# RXMIX-SE.net
KiCad netlist of a schematic drawn in Altium Designer
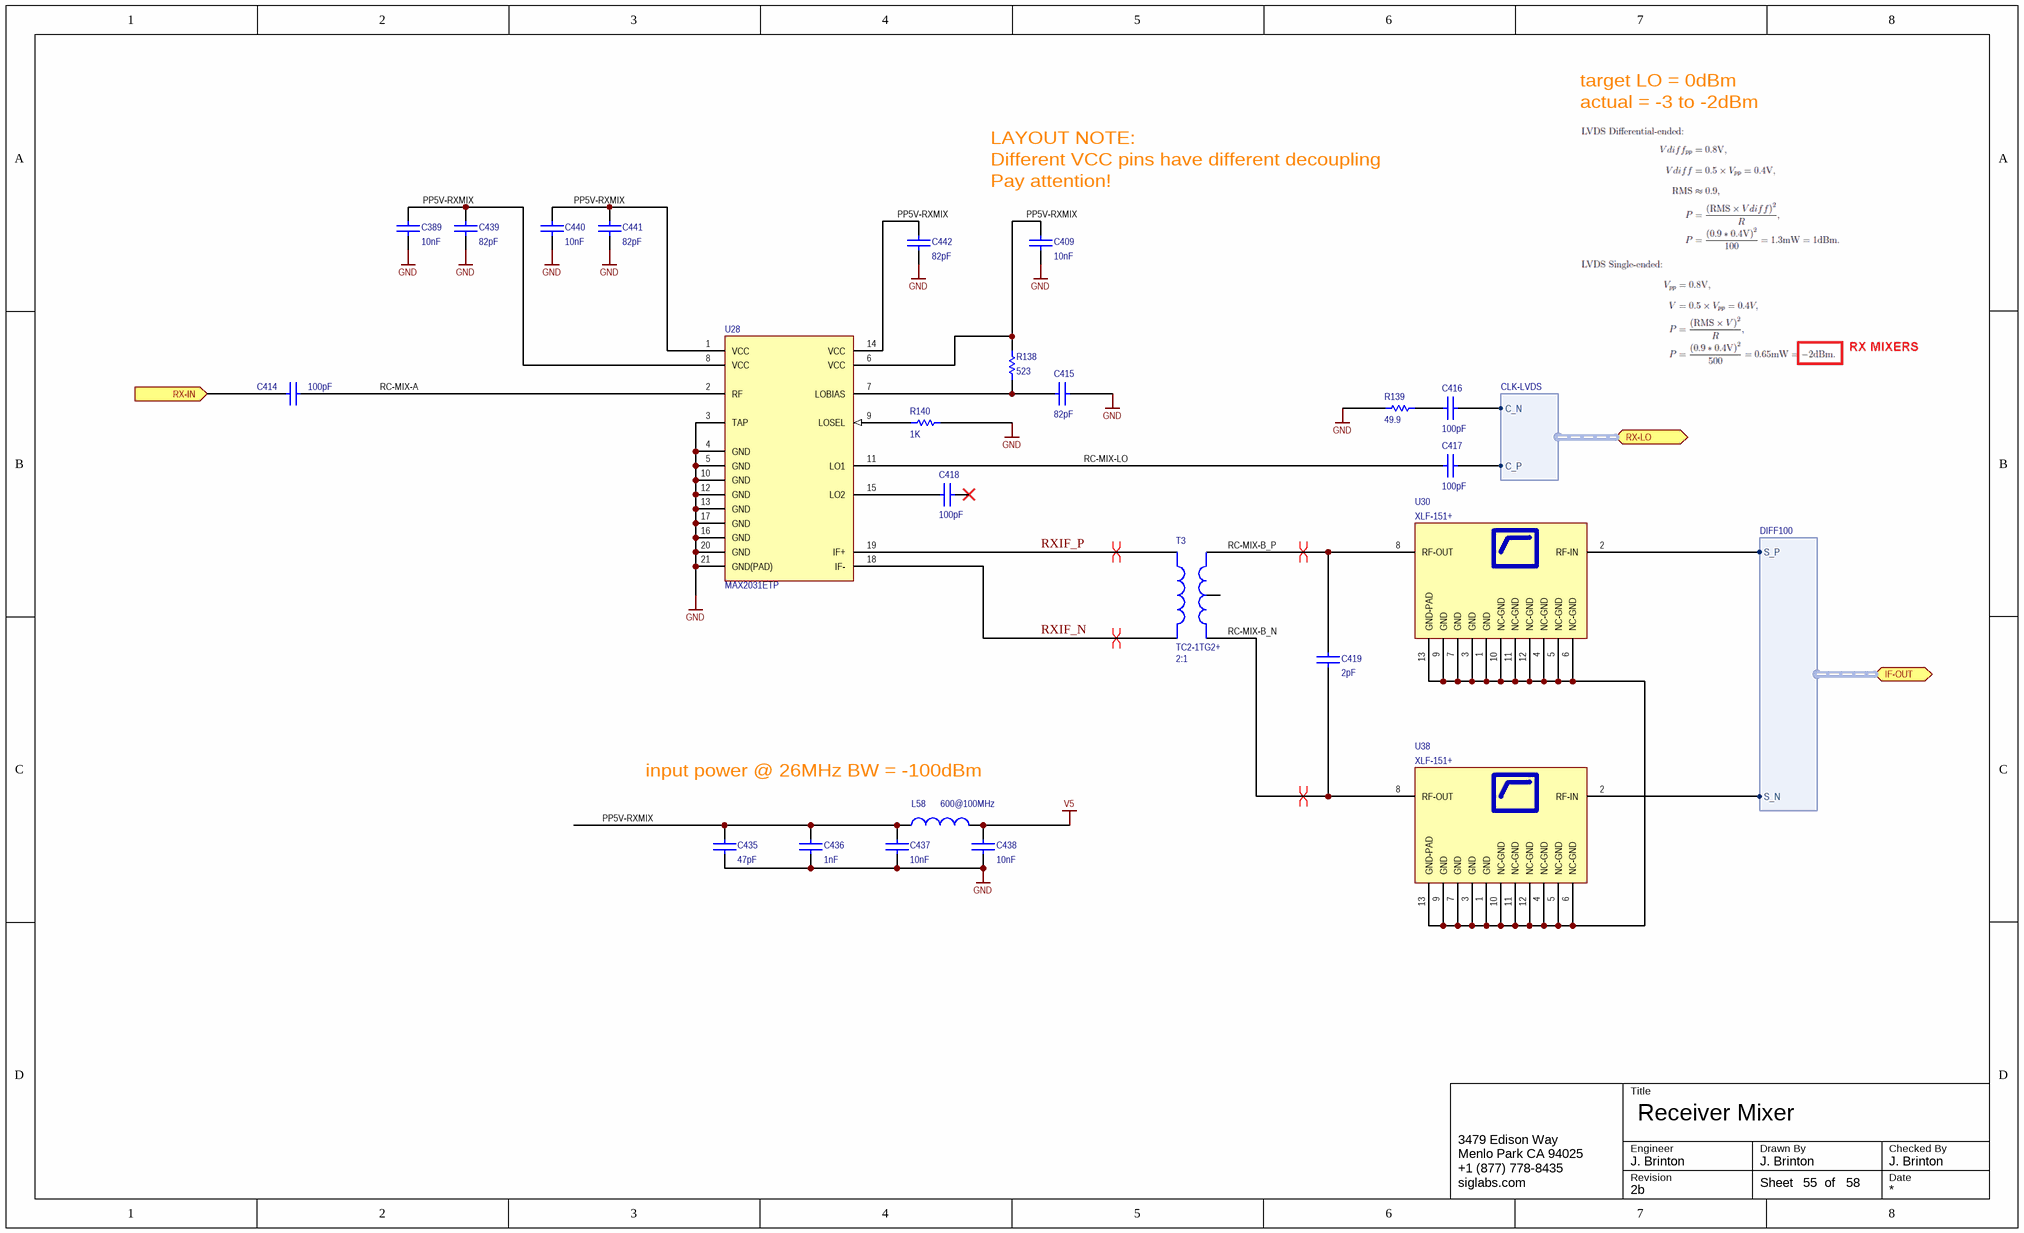
[diagram p0: RXMIX-SE.SchDoc]

(export (version "E")
  (design (tool "Eeschema 10.0.6"))
  (components
    (comp (ref "C389")
      (value "10nF")
      (footprint "generic:0402")
      (description "Ceramic Capacitor 10nF ±10% 25V X7R 0402")
      (fields (field (name "VOLTAGE") "25V") (field (name "MANUFACTURER") "Murata"))
      (libsource (lib "Graviton") (part "CAP 0402"))
    )
    (comp (ref "C409")
      (value "10nF")
      (footprint "generic:0402")
      (description "Ceramic Capacitor 10nF ±10% 25V X7R 0402")
      (fields (field (name "VOLTAGE") "25V") (field (name "MANUFACTURER") "Murata"))
      (libsource (lib "Graviton") (part "CAP 0402"))
    )
    (comp (ref "C414")
      (value "100pF")
      (footprint "0402")
      (description "Ceramic Capacitor 100pF ±1% 25V NP0 0402")
      (fields (field (name "VOLTAGE") "25V") (field (name "MANUFACTURER") "Kemet"))
      (libsource (lib "generic") (part "CAP 0603"))
    )
    (comp (ref "C415")
      (value "82pF")
      (footprint "0402")
      (description "Ceramic Capacitor 82pF ±5% 25V NP0 0402")
      (fields (field (name "VOLTAGE") "25V") (field (name "MANUFACTURER") "Vishay Vitramon"))
      (libsource (lib "generic") (part "CAP"))
    )
    (comp (ref "C416")
      (value "100pF")
      (footprint "0402")
      (description "Ceramic Capacitor 100pF ±1% 25V NP0 0402")
      (fields (field (name "MANUFACTURER") "Kemet") (field (name "VOLTAGE") "25V"))
      (libsource (lib "generic") (part "CAP 0603"))
    )
    (comp (ref "C417")
      (value "100pF")
      (footprint "0402")
      (description "Ceramic Capacitor 100pF ±1% 25V NP0 0402")
      (fields (field (name "VOLTAGE") "25V") (field (name "MANUFACTURER") "Kemet"))
      (libsource (lib "generic") (part "CAP 0603"))
    )
    (comp (ref "C418")
      (value "100pF")
      (footprint "0402")
      (description "Ceramic Capacitor 100pF ±1% 25V NP0 0402")
      (fields (field (name "MANUFACTURER") "Kemet") (field (name "VOLTAGE") "25V"))
      (libsource (lib "generic") (part "CAP 0603"))
    )
    (comp (ref "C419")
      (value "2pF")
      (footprint "generic:0402")
      (description "Ceramic Capacitor 2pF ±0.25pF 50V NP0 0402")
      (fields (field (name "VOLTAGE") "50V") (field (name "MANUFACTURER") "Murata"))
      (libsource (lib "generic") (part "CAP 0402"))
    )
    (comp (ref "C435")
      (value "47pF")
      (footprint "generic:0402")
      (description "Ceramic Capacitor 47pF ±1% 25V NP0 0402")
      (fields (field (name "VOLTAGE") "25V") (field (name "MANUFACTURER") "Kemet"))
      (libsource (lib "Graviton") (part "CAP 0402"))
    )
    (comp (ref "C436")
      (value "1nF")
      (footprint "generic:0402")
      (description "Ceramic Capacitor 1nF ±5% 50V NP0 0402")
      (fields (field (name "VOLTAGE") "50V") (field (name "MANUFACTURER") "Murata"))
      (libsource (lib "Graviton") (part "CAP 0402"))
    )
    (comp (ref "C437")
      (value "10nF")
      (footprint "generic:0402")
      (description "Ceramic Capacitor 10nF ±10% 25V X7R 0402")
      (fields (field (name "VOLTAGE") "25V") (field (name "MANUFACTURER") "Murata"))
      (libsource (lib "Graviton") (part "CAP 0402"))
    )
    (comp (ref "C438")
      (value "10nF")
      (footprint "generic:0402")
      (description "Ceramic Capacitor 10nF ±10% 25V X7R 0402")
      (fields (field (name "VOLTAGE") "25V") (field (name "MANUFACTURER") "Murata"))
      (libsource (lib "Graviton") (part "CAP 0402"))
    )
    (comp (ref "C439")
      (value "82pF")
      (footprint "0402")
      (description "Ceramic Capacitor 82pF ±5% 25V NP0 0402")
      (fields (field (name "MANUFACTURER") "Vishay Vitramon") (field (name "VOLTAGE") "25V"))
      (libsource (lib "generic") (part "CAP"))
    )
    (comp (ref "C440")
      (value "10nF")
      (footprint "generic:0402")
      (description "Ceramic Capacitor 10nF ±10% 25V X7R 0402")
      (fields (field (name "VOLTAGE") "25V") (field (name "MANUFACTURER") "Murata"))
      (libsource (lib "Graviton") (part "CAP 0402"))
    )
    (comp (ref "C441")
      (value "82pF")
      (footprint "0402")
      (description "Ceramic Capacitor 82pF ±5% 25V NP0 0402")
      (fields (field (name "VOLTAGE") "25V") (field (name "MANUFACTURER") "Vishay Vitramon"))
      (libsource (lib "generic") (part "CAP"))
    )
    (comp (ref "C442")
      (value "82pF")
      (footprint "0402")
      (description "Ceramic Capacitor 82pF ±5% 25V NP0 0402")
      (fields (field (name "MANUFACTURER") "Vishay Vitramon") (field (name "VOLTAGE") "25V"))
      (libsource (lib "generic") (part "CAP"))
    )
    (comp (ref "L58")
      (value "600@100MHz")
      (footprint "0402")
      (description "Ferrite Bead 600-Ohm @ 100MHz 900mA 0402")
      (fields (field (name "MANUFACTURER") "Murata") (field (name "TOLERANCE") "±25%"))
      (libsource (lib "Graviton") (part "IND 0402"))
    )
    (comp (ref "R138")
      (value "523")
      (footprint "generic:0603")
      (description "Thick Film Resistor 523 ±1% 0603")
      (fields (field (name "MANUFACTURER") "Yageo") (field (name "TOLERANCE") "±1%"))
      (libsource (lib "generic") (part "RES 0603"))
    )
    (comp (ref "R139")
      (value "49.9")
      (footprint "generic:0603")
      (description "Thick Film Resistor 49.9 ±1% 0603")
      (fields (field (name "MANUFACTURER") "Panasonic") (field (name "TOLERANCE") "±1%"))
      (libsource (lib "generic") (part "RES 0603"))
    )
    (comp (ref "R140")
      (value "1K")
      (footprint "generic:0402")
      (description "Thick Film Resistor 1k ±1% 0402")
      (fields (field (name "MANUFACTURER") "Yageo") (field (name "TOLERANCE") "±1%"))
      (libsource (lib "Graviton") (part "RES 0402"))
    )
    (comp (ref "T3")
      (value "2:1")
      (footprint "AT224-1A")
      (description "RF Transformer 0.4 to 500MHz SMD")
      (fields
        (field (name "MANUFACTURER P/N") "TC2-1TG2+")
        (field (name "MANUFACTURER") "Mini-Circuits")
        (field (name "Comment") "TC2-1TG2+")
      )
      (libsource (lib "phase4") (part "TC1-1TG2+"))
    )
    (comp (ref "U28")
      (value "MAX2031ETP")
      (footprint "QFN21P65_500X500X80L55X30T320N")
      (description "Upconversion/Downconversion Mixer")
      (fields (field (name "MANUFACTURER") "Maxim"))
      (libsource (lib "maxim") (part "MAX2031ETP"))
    )
    (comp (ref "U30")
      (value "XLF-151+")
      (footprint "QFN-XLF-12")
      (description "Reflectionless Low-Pass Filter, DC-150Mhz")
      (fields (field (name "MANUFACTURER") "Mini-Circuits"))
      (libsource (lib "Mini-Circuits") (part "XLF-151+"))
    )
    (comp (ref "U38")
      (value "XLF-151+")
      (footprint "QFN-XLF-12")
      (description "Reflectionless Low-Pass Filter, DC-150Mhz")
      (fields (field (name "MANUFACTURER") "Mini-Circuits"))
      (libsource (lib "Mini-Circuits") (part "XLF-151+"))
    )
  )
  (nets
    (net (code "3") (name "/C_N") (class "Default")
      (node (ref "C416") (pin "2") (pinfunction "2_2") (pintype "passive"))
    )
    (net (code "4") (name "/C_P") (class "Default")
      (node (ref "C417") (pin "2") (pinfunction "2_2") (pintype "passive"))
    )
    (net (code "5") (name "/PP5V-RXMIX") (class "Default")
      (node (ref "C389") (pin "2") (pinfunction "2_2") (pintype "passive"))
      (node (ref "C409") (pin "2") (pinfunction "2_2") (pintype "passive"))
      (node (ref "C435") (pin "2") (pinfunction "2_2") (pintype "passive"))
      (node (ref "C436") (pin "2") (pinfunction "2_2") (pintype "passive"))
      (node (ref "C437") (pin "2") (pinfunction "2_2") (pintype "passive"))
      (node (ref "C439") (pin "2") (pinfunction "2_2") (pintype "passive"))
      (node (ref "C440") (pin "2") (pinfunction "2_2") (pintype "passive"))
      (node (ref "C441") (pin "2") (pinfunction "2_2") (pintype "passive"))
      (node (ref "C442") (pin "2") (pinfunction "2_2") (pintype "passive"))
      (node (ref "L58") (pin "2") (pinfunction "2_2") (pintype "passive"))
      (node (ref "R138") (pin "1") (pinfunction "1_1") (pintype "passive"))
      (node (ref "U28") (pin "1") (pinfunction "VCC_1") (pintype "power_in"))
      (node (ref "U28") (pin "14") (pinfunction "VCC_14") (pintype "power_in"))
      (node (ref "U28") (pin "6") (pinfunction "VCC_6") (pintype "power_in"))
      (node (ref "U28") (pin "8") (pinfunction "VCC_8") (pintype "power_in"))
    )
    (net (code "6") (name "/RC-MIX-A") (class "Default")
      (node (ref "C414") (pin "2") (pinfunction "2_2") (pintype "passive"))
      (node (ref "U28") (pin "2") (pinfunction "RF_2") (pintype "passive"))
    )
    (net (code "7") (name "/RC-MIX-B_N") (class "Default")
      (node (ref "C419") (pin "1") (pinfunction "1_1") (pintype "passive"))
      (node (ref "T3") (pin "1") (pinfunction "Sec+_1") (pintype "passive"))
      (node (ref "U38") (pin "8") (pinfunction "RF-OUT_8") (pintype "passive"))
    )
    (net (code "8") (name "/RC-MIX-B_P") (class "Default")
      (node (ref "C419") (pin "2") (pinfunction "2_2") (pintype "passive"))
      (node (ref "T3") (pin "3") (pinfunction "Sec-_3") (pintype "passive"))
      (node (ref "U30") (pin "8") (pinfunction "RF-OUT_8") (pintype "passive"))
    )
    (net (code "9") (name "/RC-MIX-LO") (class "Default")
      (node (ref "C417") (pin "1") (pinfunction "1_1") (pintype "passive"))
      (node (ref "U28") (pin "11") (pinfunction "LO1_11") (pintype "passive"))
    )
    (net (code "10") (name "/RX-IN") (class "Default")
      (node (ref "C414") (pin "1") (pinfunction "1_1") (pintype "passive"))
    )
    (net (code "11") (name "/RXIF_N") (class "Default")
      (node (ref "T3") (pin "6") (pinfunction "Pri+_6") (pintype "passive"))
      (node (ref "U28") (pin "18") (pinfunction "IF-_18") (pintype "passive"))
    )
    (net (code "12") (name "/RXIF_P") (class "Default")
      (node (ref "T3") (pin "4") (pinfunction "Pri-_4") (pintype "passive"))
      (node (ref "U28") (pin "19") (pinfunction "IF+_19") (pintype "passive"))
    )
    (net (code "13") (name "/S_N") (class "Default")
      (node (ref "U38") (pin "2") (pinfunction "RF-IN_2") (pintype "passive"))
    )
    (net (code "14") (name "/S_P") (class "Default")
      (node (ref "U30") (pin "2") (pinfunction "RF-IN_2") (pintype "passive"))
    )
    (net (code "17") (name "GND") (class "Default")
      (node (ref "C389") (pin "1") (pinfunction "1_1") (pintype "passive"))
      (node (ref "C409") (pin "1") (pinfunction "1_1") (pintype "passive"))
      (node (ref "C415") (pin "2") (pinfunction "2_2") (pintype "passive"))
      (node (ref "C435") (pin "1") (pinfunction "1_1") (pintype "passive"))
      (node (ref "C436") (pin "1") (pinfunction "1_1") (pintype "passive"))
      (node (ref "C437") (pin "1") (pinfunction "1_1") (pintype "passive"))
      (node (ref "C438") (pin "1") (pinfunction "1_1") (pintype "passive"))
      (node (ref "C439") (pin "1") (pinfunction "1_1") (pintype "passive"))
      (node (ref "C440") (pin "1") (pinfunction "1_1") (pintype "passive"))
      (node (ref "C441") (pin "1") (pinfunction "1_1") (pintype "passive"))
      (node (ref "C442") (pin "1") (pinfunction "1_1") (pintype "passive"))
      (node (ref "R139") (pin "1") (pinfunction "1_1") (pintype "passive"))
      (node (ref "R140") (pin "2") (pinfunction "2_2") (pintype "passive"))
      (node (ref "U28") (pin "10") (pinfunction "GND_10") (pintype "power_in"))
      (node (ref "U28") (pin "12") (pinfunction "GND_12") (pintype "power_in"))
      (node (ref "U28") (pin "13") (pinfunction "GND_13") (pintype "power_in"))
      (node (ref "U28") (pin "16") (pinfunction "GND_16") (pintype "power_in"))
      (node (ref "U28") (pin "17") (pinfunction "GND_17") (pintype "power_in"))
      (node (ref "U28") (pin "20") (pinfunction "GND_20") (pintype "power_in"))
      (node (ref "U28") (pin "21") (pinfunction "GND(PAD)_21") (pintype "power_in"))
      (node (ref "U28") (pin "3") (pinfunction "TAP_3") (pintype "passive"))
      (node (ref "U28") (pin "4") (pinfunction "GND_4") (pintype "power_in"))
      (node (ref "U28") (pin "5") (pinfunction "GND_5") (pintype "power_in"))
    )
    (net (code "18") (name "Net-(C416-Pad1)") (class "Default")
      (node (ref "C416") (pin "1") (pinfunction "1_1") (pintype "passive"))
      (node (ref "R139") (pin "2") (pinfunction "2_2") (pintype "passive"))
    )
    (net (code "19") (name "Net-(U28-LO2)") (class "Default")
      (node (ref "C418") (pin "1") (pinfunction "1_1") (pintype "passive"))
      (node (ref "U28") (pin "15") (pinfunction "LO2_15") (pintype "passive"))
    )
    (net (code "20") (name "Net-(U28-LOBIAS)") (class "Default")
      (node (ref "C415") (pin "1") (pinfunction "1_1") (pintype "passive"))
      (node (ref "R138") (pin "2") (pinfunction "2_2") (pintype "passive"))
      (node (ref "U28") (pin "7") (pinfunction "LOBIAS_7") (pintype "passive"))
    )
    (net (code "21") (name "Net-(U28-LOSEL)") (class "Default")
      (node (ref "R140") (pin "1") (pinfunction "1_1") (pintype "passive"))
      (node (ref "U28") (pin "9") (pinfunction "LOSEL_9") (pintype "input"))
    )
    (net (code "22") (name "Net-(U30-GND-PAD)") (class "Default")
      (node (ref "U30") (pin "1") (pinfunction "GND_1") (pintype "passive"))
      (node (ref "U30") (pin "10") (pinfunction "NC-GND_10") (pintype "passive"))
      (node (ref "U30") (pin "11") (pinfunction "NC-GND_11") (pintype "passive"))
      (node (ref "U30") (pin "12") (pinfunction "NC-GND_12") (pintype "passive"))
      (node (ref "U30") (pin "13") (pinfunction "GND-PAD_13") (pintype "passive"))
      (node (ref "U30") (pin "3") (pinfunction "GND_3") (pintype "passive"))
      (node (ref "U30") (pin "4") (pinfunction "NC-GND_4") (pintype "passive"))
      (node (ref "U30") (pin "5") (pinfunction "NC-GND_5") (pintype "passive"))
      (node (ref "U30") (pin "6") (pinfunction "NC-GND_6") (pintype "passive"))
      (node (ref "U30") (pin "7") (pinfunction "GND_7") (pintype "passive"))
      (node (ref "U30") (pin "9") (pinfunction "GND_9") (pintype "passive"))
      (node (ref "U38") (pin "1") (pinfunction "GND_1") (pintype "passive"))
      (node (ref "U38") (pin "10") (pinfunction "NC-GND_10") (pintype "passive"))
      (node (ref "U38") (pin "11") (pinfunction "NC-GND_11") (pintype "passive"))
      (node (ref "U38") (pin "12") (pinfunction "NC-GND_12") (pintype "passive"))
      (node (ref "U38") (pin "13") (pinfunction "GND-PAD_13") (pintype "passive"))
      (node (ref "U38") (pin "3") (pinfunction "GND_3") (pintype "passive"))
      (node (ref "U38") (pin "4") (pinfunction "NC-GND_4") (pintype "passive"))
      (node (ref "U38") (pin "5") (pinfunction "NC-GND_5") (pintype "passive"))
      (node (ref "U38") (pin "6") (pinfunction "NC-GND_6") (pintype "passive"))
      (node (ref "U38") (pin "7") (pinfunction "GND_7") (pintype "passive"))
      (node (ref "U38") (pin "9") (pinfunction "GND_9") (pintype "passive"))
    )
    (net (code "23") (name "V5") (class "Default")
      (node (ref "C438") (pin "2") (pinfunction "2_2") (pintype "passive"))
      (node (ref "L58") (pin "1") (pinfunction "1_1") (pintype "passive"))
    )
    (net (code "24") (name "unconnected-(C418-Pad2)") (class "Default")
      (node (ref "C418") (pin "2") (pinfunction "2_2") (pintype "passive+no_connect"))
    )
    (net (code "25") (name "unconnected-(T3-SecCT-Pad2)") (class "Default")
      (node (ref "T3") (pin "2") (pinfunction "SecCT_2") (pintype "passive"))
    )
  )
)
